# Open_Reactor_Control_System_-_IO_Connect.net
KiCad netlist of a schematic drawn in Altium Designer
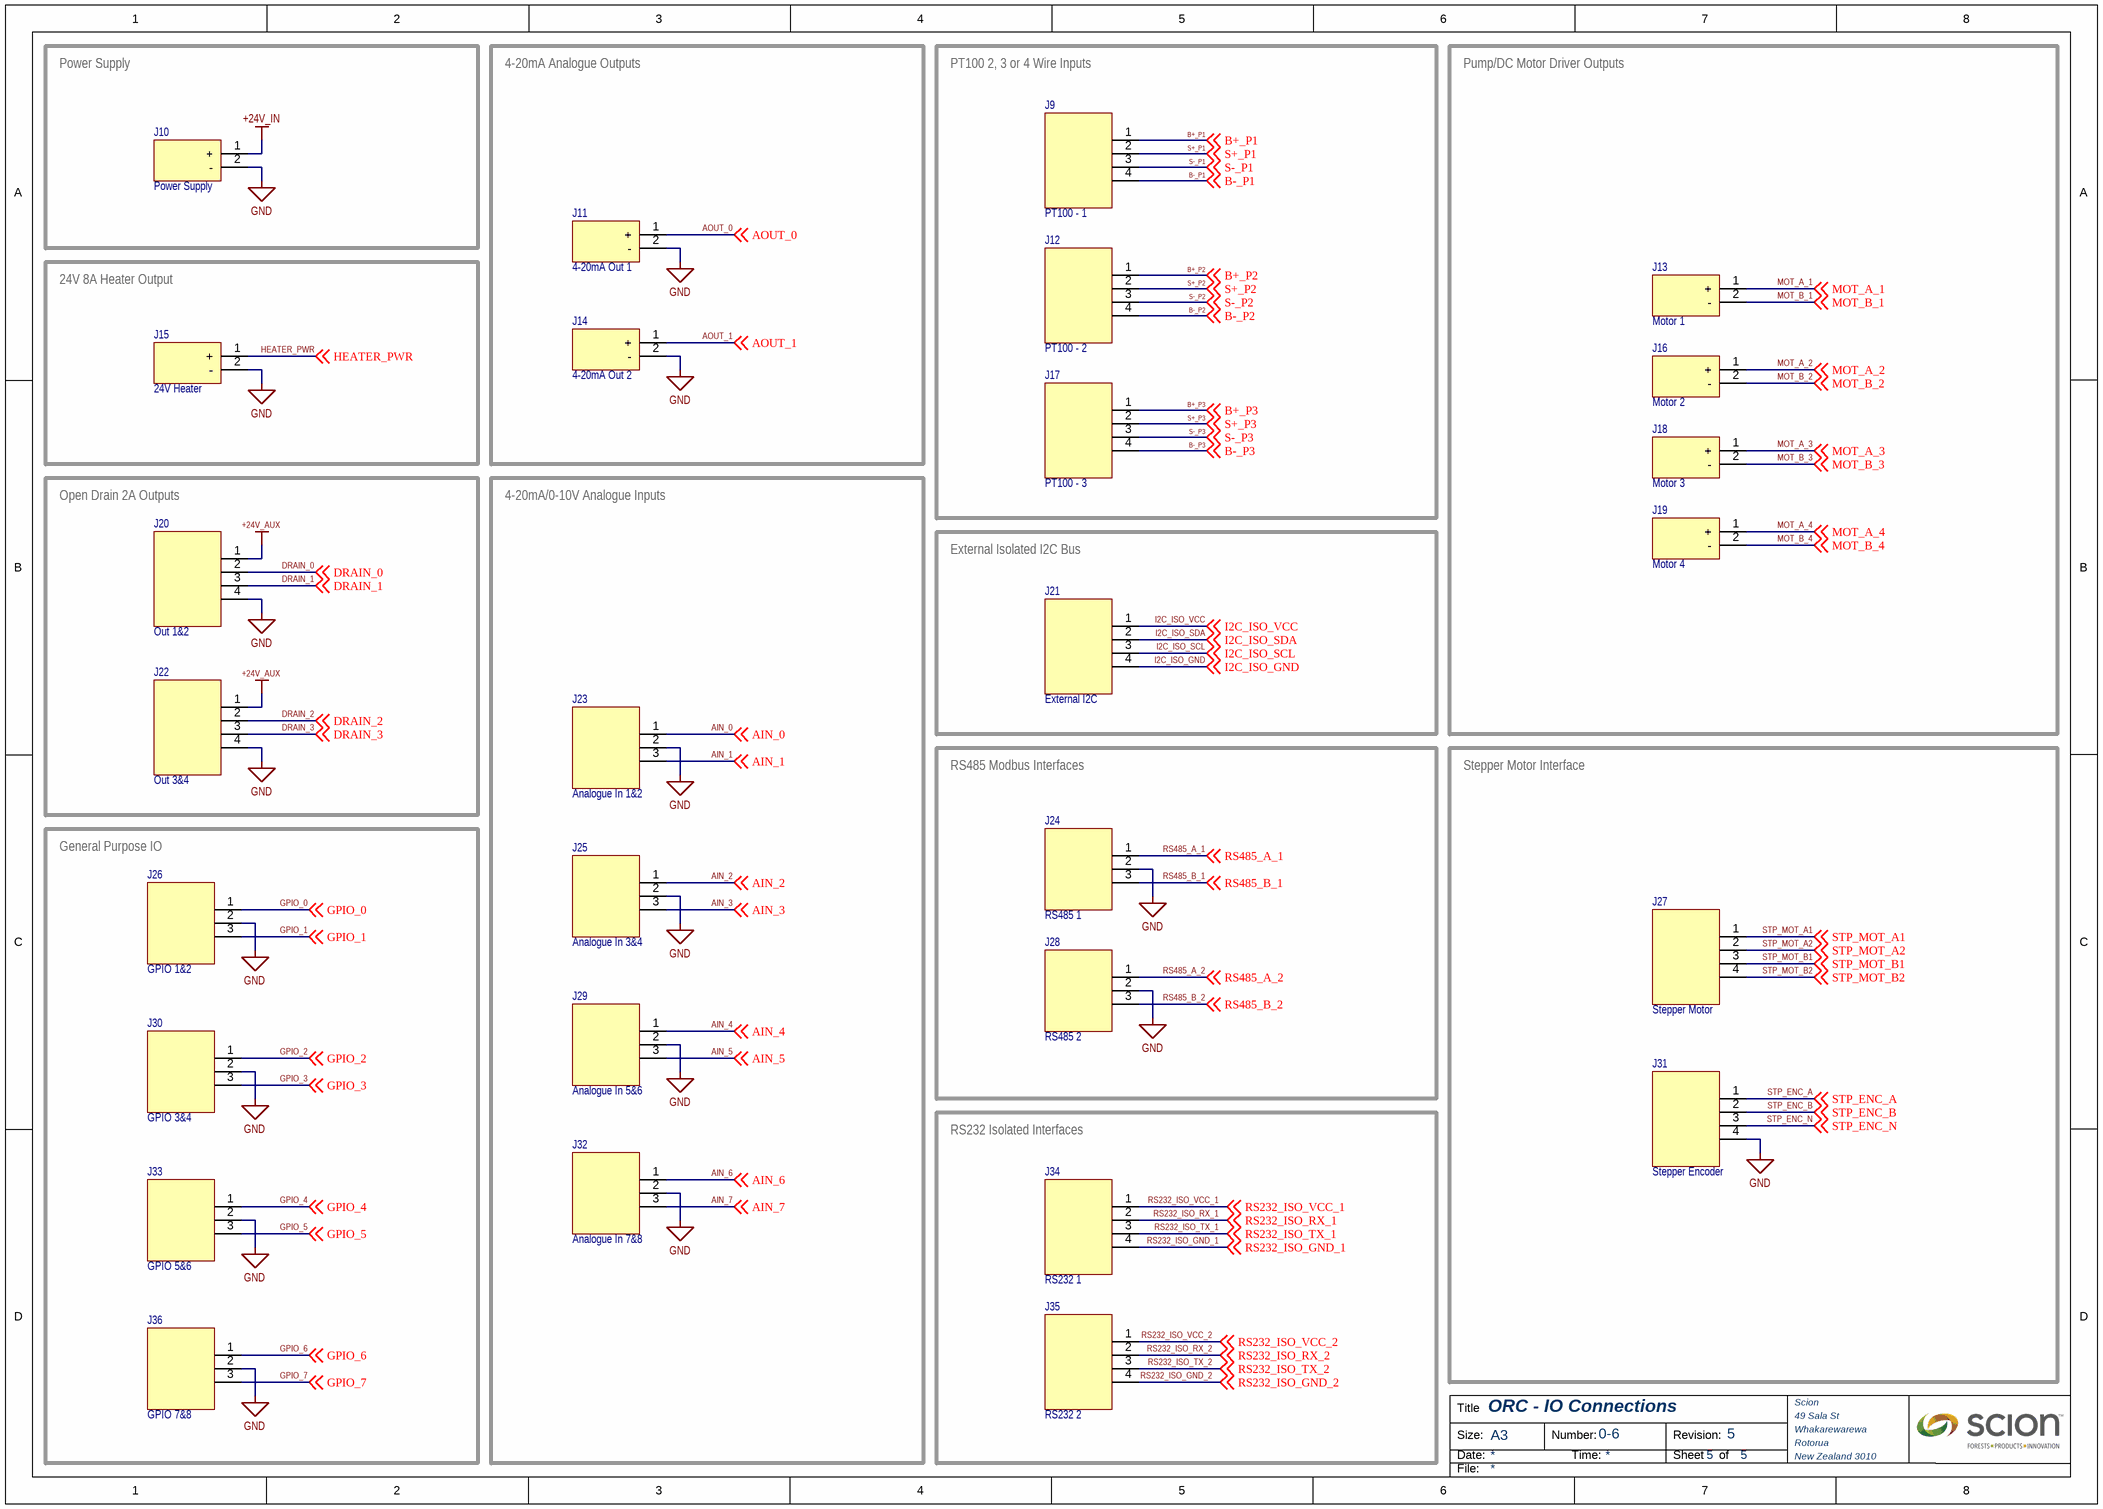
[diagram p0: Open Reactor Control System - IO Connections.SchDoc]

(export (version "E")
  (design (tool "Eeschema 10.0.6"))
  (components
    (comp (ref "J9")
      (value "PT100 - 1")
      (footprint "4_Pin 3.81mm Molex 395111-004")
      (description "4 Pin Connector")
      (libsource (lib "Scion Research") (part "CMP-002-00078-6"))
    )
    (comp (ref "J10")
      (value "Power Supply")
      (footprint "2_Pin 3.81mm Molex 395111-002")
      (description "2 Pin Connector")
      (libsource (lib "Scion Research") (part "CMP-002-00074-8"))
    )
    (comp (ref "J11")
      (value "4-20mA Out 1")
      (footprint "2_Pin 3.81mm Molex 395111-002")
      (description "2 Pin Connector")
      (libsource (lib "Scion Research") (part "CMP-002-00074-8"))
    )
    (comp (ref "J12")
      (value "PT100 - 2")
      (footprint "4_Pin 3.81mm Molex 395111-004")
      (description "4 Pin Connector")
      (libsource (lib "Scion Research") (part "CMP-002-00078-6"))
    )
    (comp (ref "J13")
      (value "Motor 1")
      (footprint "2_Pin 3.81mm Molex 395111-002")
      (description "2 Pin Connector")
      (libsource (lib "Scion Research") (part "CMP-002-00074-8"))
    )
    (comp (ref "J14")
      (value "4-20mA Out 2")
      (footprint "2_Pin 3.81mm Molex 395111-002")
      (description "2 Pin Connector")
      (libsource (lib "Scion Research") (part "CMP-002-00074-8"))
    )
    (comp (ref "J15")
      (value "24V Heater")
      (footprint "2_Pin 3.81mm Molex 395111-002")
      (description "2 Pin Connector")
      (libsource (lib "Scion Research") (part "CMP-002-00074-8"))
    )
    (comp (ref "J16")
      (value "Motor 2")
      (footprint "2_Pin 3.81mm Molex 395111-002")
      (description "2 Pin Connector")
      (libsource (lib "Scion Research") (part "CMP-002-00074-8"))
    )
    (comp (ref "J17")
      (value "PT100 - 3")
      (footprint "4_Pin 3.81mm Molex 395111-004")
      (description "4 Pin Connector")
      (libsource (lib "Scion Research") (part "CMP-002-00078-6"))
    )
    (comp (ref "J18")
      (value "Motor 3")
      (footprint "2_Pin 3.81mm Molex 395111-002")
      (description "2 Pin Connector")
      (libsource (lib "Scion Research") (part "CMP-002-00074-8"))
    )
    (comp (ref "J19")
      (value "Motor 4")
      (footprint "2_Pin 3.81mm Molex 395111-002")
      (description "2 Pin Connector")
      (libsource (lib "Scion Research") (part "CMP-002-00074-8"))
    )
    (comp (ref "J20")
      (value "Out 1&2")
      (footprint "4_Pin 3.81mm Molex 395111-004")
      (description "4 Pin Connector")
      (libsource (lib "Scion Research") (part "CMP-002-00078-6"))
    )
    (comp (ref "J21")
      (value "External I2C")
      (footprint "4_Pin 3.81mm Molex 395111-004")
      (description "4 Pin Connector")
      (libsource (lib "Scion Research") (part "CMP-002-00078-6"))
    )
    (comp (ref "J22")
      (value "Out 3&4")
      (footprint "4_Pin 3.81mm Molex 395111-004")
      (description "4 Pin Connector")
      (libsource (lib "Scion Research") (part "CMP-002-00078-6"))
    )
    (comp (ref "J23")
      (value "Analogue In 1&2")
      (footprint "3_Pin 3.81mm Molex 395111-003")
      (description "3 Pin Connector")
      (libsource (lib "Scion Research") (part "CMP-002-00075-6"))
    )
    (comp (ref "J24")
      (value "RS485 1")
      (footprint "3_Pin 3.81mm Molex 395111-003")
      (description "3 Pin Connector")
      (libsource (lib "Scion Research") (part "CMP-002-00075-6"))
    )
    (comp (ref "J25")
      (value "Analogue In 3&4")
      (footprint "3_Pin 3.81mm Molex 395111-003")
      (description "3 Pin Connector")
      (libsource (lib "Scion Research") (part "CMP-002-00075-6"))
    )
    (comp (ref "J26")
      (value "GPIO 1&2")
      (footprint "3_Pin 3.81mm Molex 395111-003")
      (description "3 Pin Connector")
      (libsource (lib "Scion Research") (part "CMP-002-00075-6"))
    )
    (comp (ref "J27")
      (value "Stepper Motor")
      (footprint "4_Pin 3.81mm Molex 395111-004")
      (description "4 Pin Connector")
      (libsource (lib "Scion Research") (part "CMP-002-00078-6"))
    )
    (comp (ref "J28")
      (value "RS485 2")
      (footprint "3_Pin 3.81mm Molex 395111-003")
      (description "3 Pin Connector")
      (libsource (lib "Scion Research") (part "CMP-002-00075-6"))
    )
    (comp (ref "J29")
      (value "Analogue In 5&6")
      (footprint "3_Pin 3.81mm Molex 395111-003")
      (description "3 Pin Connector")
      (libsource (lib "Scion Research") (part "CMP-002-00075-6"))
    )
    (comp (ref "J30")
      (value "GPIO 3&4")
      (footprint "3_Pin 3.81mm Molex 395111-003")
      (description "3 Pin Connector")
      (libsource (lib "Scion Research") (part "CMP-002-00075-6"))
    )
    (comp (ref "J31")
      (value "Stepper Encoder")
      (footprint "4_Pin 3.81mm Molex 395111-004")
      (description "4 Pin Connector")
      (libsource (lib "Scion Research") (part "CMP-002-00078-6"))
    )
    (comp (ref "J32")
      (value "Analogue In 7&8")
      (footprint "3_Pin 3.81mm Molex 395111-003")
      (description "3 Pin Connector")
      (libsource (lib "Scion Research") (part "CMP-002-00075-6"))
    )
    (comp (ref "J33")
      (value "GPIO 5&6")
      (footprint "3_Pin 3.81mm Molex 395111-003")
      (description "3 Pin Connector")
      (libsource (lib "Scion Research") (part "CMP-002-00075-6"))
    )
    (comp (ref "J34")
      (value "RS232 1")
      (footprint "4_Pin 3.81mm Molex 395111-004")
      (description "4 Pin Connector")
      (libsource (lib "Scion Research") (part "CMP-002-00078-6"))
    )
    (comp (ref "J35")
      (value "RS232 2")
      (footprint "4_Pin 3.81mm Molex 395111-004")
      (description "4 Pin Connector")
      (libsource (lib "Scion Research") (part "CMP-002-00078-6"))
    )
    (comp (ref "J36")
      (value "GPIO 7&8")
      (footprint "3_Pin 3.81mm Molex 395111-003")
      (description "3 Pin Connector")
      (libsource (lib "Scion Research") (part "CMP-002-00075-6"))
    )
  )
  (nets
    (net (code "1") (name "+24V_AUX") (class "Default")
      (node (ref "J20") (pin "1") (pinfunction "1_1") (pintype "passive"))
      (node (ref "J22") (pin "1") (pinfunction "1_1") (pintype "passive"))
    )
    (net (code "2") (name "+24V_IN") (class "Default")
      (node (ref "J10") (pin "1") (pinfunction "+_1") (pintype "passive"))
    )
    (net (code "3") (name "AIN_0") (class "Default")
      (node (ref "J23") (pin "1") (pinfunction "1_1") (pintype "passive"))
    )
    (net (code "4") (name "AIN_1") (class "Default")
      (node (ref "J23") (pin "3") (pinfunction "3_3") (pintype "passive"))
    )
    (net (code "5") (name "AIN_2") (class "Default")
      (node (ref "J25") (pin "1") (pinfunction "1_1") (pintype "passive"))
    )
    (net (code "6") (name "AIN_3") (class "Default")
      (node (ref "J25") (pin "3") (pinfunction "3_3") (pintype "passive"))
    )
    (net (code "7") (name "AIN_4") (class "Default")
      (node (ref "J29") (pin "1") (pinfunction "1_1") (pintype "passive"))
    )
    (net (code "8") (name "AIN_5") (class "Default")
      (node (ref "J29") (pin "3") (pinfunction "3_3") (pintype "passive"))
    )
    (net (code "9") (name "AIN_6") (class "Default")
      (node (ref "J32") (pin "1") (pinfunction "1_1") (pintype "passive"))
    )
    (net (code "10") (name "AIN_7") (class "Default")
      (node (ref "J32") (pin "3") (pinfunction "3_3") (pintype "passive"))
    )
    (net (code "11") (name "AOUT_0") (class "Default")
      (node (ref "J11") (pin "1") (pinfunction "+_1") (pintype "passive"))
    )
    (net (code "12") (name "AOUT_1") (class "Default")
      (node (ref "J14") (pin "1") (pinfunction "+_1") (pintype "passive"))
    )
    (net (code "13") (name "B+_P1") (class "Default")
      (node (ref "J9") (pin "1") (pinfunction "1_1") (pintype "passive"))
    )
    (net (code "14") (name "B+_P2") (class "Default")
      (node (ref "J12") (pin "1") (pinfunction "1_1") (pintype "passive"))
    )
    (net (code "15") (name "B+_P3") (class "Default")
      (node (ref "J17") (pin "1") (pinfunction "1_1") (pintype "passive"))
    )
    (net (code "16") (name "B-_P1") (class "Default")
      (node (ref "J9") (pin "4") (pinfunction "4_4") (pintype "passive"))
    )
    (net (code "17") (name "B-_P2") (class "Default")
      (node (ref "J12") (pin "4") (pinfunction "4_4") (pintype "passive"))
    )
    (net (code "18") (name "B-_P3") (class "Default")
      (node (ref "J17") (pin "4") (pinfunction "4_4") (pintype "passive"))
    )
    (net (code "19") (name "DRAIN_0") (class "Default")
      (node (ref "J20") (pin "2") (pinfunction "2_2") (pintype "passive"))
    )
    (net (code "20") (name "DRAIN_1") (class "Default")
      (node (ref "J20") (pin "3") (pinfunction "3_3") (pintype "passive"))
    )
    (net (code "21") (name "DRAIN_2") (class "Default")
      (node (ref "J22") (pin "2") (pinfunction "2_2") (pintype "passive"))
    )
    (net (code "22") (name "DRAIN_3") (class "Default")
      (node (ref "J22") (pin "3") (pinfunction "3_3") (pintype "passive"))
    )
    (net (code "23") (name "GND") (class "Default")
      (node (ref "J10") (pin "2") (pinfunction "-_2") (pintype "passive"))
      (node (ref "J11") (pin "2") (pinfunction "-_2") (pintype "passive"))
      (node (ref "J14") (pin "2") (pinfunction "-_2") (pintype "passive"))
      (node (ref "J15") (pin "2") (pinfunction "-_2") (pintype "passive"))
      (node (ref "J20") (pin "4") (pinfunction "4_4") (pintype "passive"))
      (node (ref "J22") (pin "4") (pinfunction "4_4") (pintype "passive"))
      (node (ref "J23") (pin "2") (pinfunction "2_2") (pintype "passive"))
      (node (ref "J24") (pin "2") (pinfunction "2_2") (pintype "passive"))
      (node (ref "J25") (pin "2") (pinfunction "2_2") (pintype "passive"))
      (node (ref "J26") (pin "2") (pinfunction "2_2") (pintype "passive"))
      (node (ref "J28") (pin "2") (pinfunction "2_2") (pintype "passive"))
      (node (ref "J29") (pin "2") (pinfunction "2_2") (pintype "passive"))
      (node (ref "J30") (pin "2") (pinfunction "2_2") (pintype "passive"))
      (node (ref "J31") (pin "4") (pinfunction "4_4") (pintype "passive"))
      (node (ref "J32") (pin "2") (pinfunction "2_2") (pintype "passive"))
      (node (ref "J33") (pin "2") (pinfunction "2_2") (pintype "passive"))
      (node (ref "J36") (pin "2") (pinfunction "2_2") (pintype "passive"))
    )
    (net (code "24") (name "GPIO_0") (class "Default")
      (node (ref "J26") (pin "1") (pinfunction "1_1") (pintype "passive"))
    )
    (net (code "25") (name "GPIO_1") (class "Default")
      (node (ref "J26") (pin "3") (pinfunction "3_3") (pintype "passive"))
    )
    (net (code "26") (name "GPIO_2") (class "Default")
      (node (ref "J30") (pin "1") (pinfunction "1_1") (pintype "passive"))
    )
    (net (code "27") (name "GPIO_3") (class "Default")
      (node (ref "J30") (pin "3") (pinfunction "3_3") (pintype "passive"))
    )
    (net (code "28") (name "GPIO_4") (class "Default")
      (node (ref "J33") (pin "1") (pinfunction "1_1") (pintype "passive"))
    )
    (net (code "29") (name "GPIO_5") (class "Default")
      (node (ref "J33") (pin "3") (pinfunction "3_3") (pintype "passive"))
    )
    (net (code "30") (name "GPIO_6") (class "Default")
      (node (ref "J36") (pin "1") (pinfunction "1_1") (pintype "passive"))
    )
    (net (code "31") (name "GPIO_7") (class "Default")
      (node (ref "J36") (pin "3") (pinfunction "3_3") (pintype "passive"))
    )
    (net (code "32") (name "HEATER_PWR") (class "Default")
      (node (ref "J15") (pin "1") (pinfunction "+_1") (pintype "passive"))
    )
    (net (code "33") (name "I2C_ISO_GND") (class "Default")
      (node (ref "J21") (pin "4") (pinfunction "4_4") (pintype "passive"))
    )
    (net (code "34") (name "I2C_ISO_SCL") (class "Default")
      (node (ref "J21") (pin "3") (pinfunction "3_3") (pintype "passive"))
    )
    (net (code "35") (name "I2C_ISO_SDA") (class "Default")
      (node (ref "J21") (pin "2") (pinfunction "2_2") (pintype "passive"))
    )
    (net (code "36") (name "I2C_ISO_VCC") (class "Default")
      (node (ref "J21") (pin "1") (pinfunction "1_1") (pintype "passive"))
    )
    (net (code "37") (name "MOT_A_1") (class "Default")
      (node (ref "J13") (pin "1") (pinfunction "+_1") (pintype "passive"))
    )
    (net (code "38") (name "MOT_A_2") (class "Default")
      (node (ref "J16") (pin "1") (pinfunction "+_1") (pintype "passive"))
    )
    (net (code "39") (name "MOT_A_3") (class "Default")
      (node (ref "J18") (pin "1") (pinfunction "+_1") (pintype "passive"))
    )
    (net (code "40") (name "MOT_A_4") (class "Default")
      (node (ref "J19") (pin "1") (pinfunction "+_1") (pintype "passive"))
    )
    (net (code "41") (name "MOT_B_1") (class "Default")
      (node (ref "J13") (pin "2") (pinfunction "-_2") (pintype "passive"))
    )
    (net (code "42") (name "MOT_B_2") (class "Default")
      (node (ref "J16") (pin "2") (pinfunction "-_2") (pintype "passive"))
    )
    (net (code "43") (name "MOT_B_3") (class "Default")
      (node (ref "J18") (pin "2") (pinfunction "-_2") (pintype "passive"))
    )
    (net (code "44") (name "MOT_B_4") (class "Default")
      (node (ref "J19") (pin "2") (pinfunction "-_2") (pintype "passive"))
    )
    (net (code "45") (name "RS232_ISO_GND_1") (class "Default")
      (node (ref "J34") (pin "4") (pinfunction "4_4") (pintype "passive"))
    )
    (net (code "46") (name "RS232_ISO_GND_2") (class "Default")
      (node (ref "J35") (pin "4") (pinfunction "4_4") (pintype "passive"))
    )
    (net (code "47") (name "RS232_ISO_RX_1") (class "Default")
      (node (ref "J34") (pin "2") (pinfunction "2_2") (pintype "passive"))
    )
    (net (code "48") (name "RS232_ISO_RX_2") (class "Default")
      (node (ref "J35") (pin "2") (pinfunction "2_2") (pintype "passive"))
    )
    (net (code "49") (name "RS232_ISO_TX_1") (class "Default")
      (node (ref "J34") (pin "3") (pinfunction "3_3") (pintype "passive"))
    )
    (net (code "50") (name "RS232_ISO_TX_2") (class "Default")
      (node (ref "J35") (pin "3") (pinfunction "3_3") (pintype "passive"))
    )
    (net (code "51") (name "RS232_ISO_VCC_1") (class "Default")
      (node (ref "J34") (pin "1") (pinfunction "1_1") (pintype "passive"))
    )
    (net (code "52") (name "RS232_ISO_VCC_2") (class "Default")
      (node (ref "J35") (pin "1") (pinfunction "1_1") (pintype "passive"))
    )
    (net (code "53") (name "RS485_A_1") (class "Default")
      (node (ref "J24") (pin "1") (pinfunction "1_1") (pintype "passive"))
    )
    (net (code "54") (name "RS485_A_2") (class "Default")
      (node (ref "J28") (pin "1") (pinfunction "1_1") (pintype "passive"))
    )
    (net (code "55") (name "RS485_B_1") (class "Default")
      (node (ref "J24") (pin "3") (pinfunction "3_3") (pintype "passive"))
    )
    (net (code "56") (name "RS485_B_2") (class "Default")
      (node (ref "J28") (pin "3") (pinfunction "3_3") (pintype "passive"))
    )
    (net (code "57") (name "S+_P1") (class "Default")
      (node (ref "J9") (pin "2") (pinfunction "2_2") (pintype "passive"))
    )
    (net (code "58") (name "S+_P2") (class "Default")
      (node (ref "J12") (pin "2") (pinfunction "2_2") (pintype "passive"))
    )
    (net (code "59") (name "S+_P3") (class "Default")
      (node (ref "J17") (pin "2") (pinfunction "2_2") (pintype "passive"))
    )
    (net (code "60") (name "S-_P1") (class "Default")
      (node (ref "J9") (pin "3") (pinfunction "3_3") (pintype "passive"))
    )
    (net (code "61") (name "S-_P2") (class "Default")
      (node (ref "J12") (pin "3") (pinfunction "3_3") (pintype "passive"))
    )
    (net (code "62") (name "S-_P3") (class "Default")
      (node (ref "J17") (pin "3") (pinfunction "3_3") (pintype "passive"))
    )
    (net (code "63") (name "STP_ENC_A") (class "Default")
      (node (ref "J31") (pin "1") (pinfunction "1_1") (pintype "passive"))
    )
    (net (code "64") (name "STP_ENC_B") (class "Default")
      (node (ref "J31") (pin "2") (pinfunction "2_2") (pintype "passive"))
    )
    (net (code "65") (name "STP_ENC_N") (class "Default")
      (node (ref "J31") (pin "3") (pinfunction "3_3") (pintype "passive"))
    )
    (net (code "66") (name "STP_MOT_A1") (class "Default")
      (node (ref "J27") (pin "1") (pinfunction "1_1") (pintype "passive"))
    )
    (net (code "67") (name "STP_MOT_A2") (class "Default")
      (node (ref "J27") (pin "2") (pinfunction "2_2") (pintype "passive"))
    )
    (net (code "68") (name "STP_MOT_B1") (class "Default")
      (node (ref "J27") (pin "3") (pinfunction "3_3") (pintype "passive"))
    )
    (net (code "69") (name "STP_MOT_B2") (class "Default")
      (node (ref "J27") (pin "4") (pinfunction "4_4") (pintype "passive"))
    )
  )
)
